# Schematico.net
KiCad netlist of a schematic drawn in EAGLE
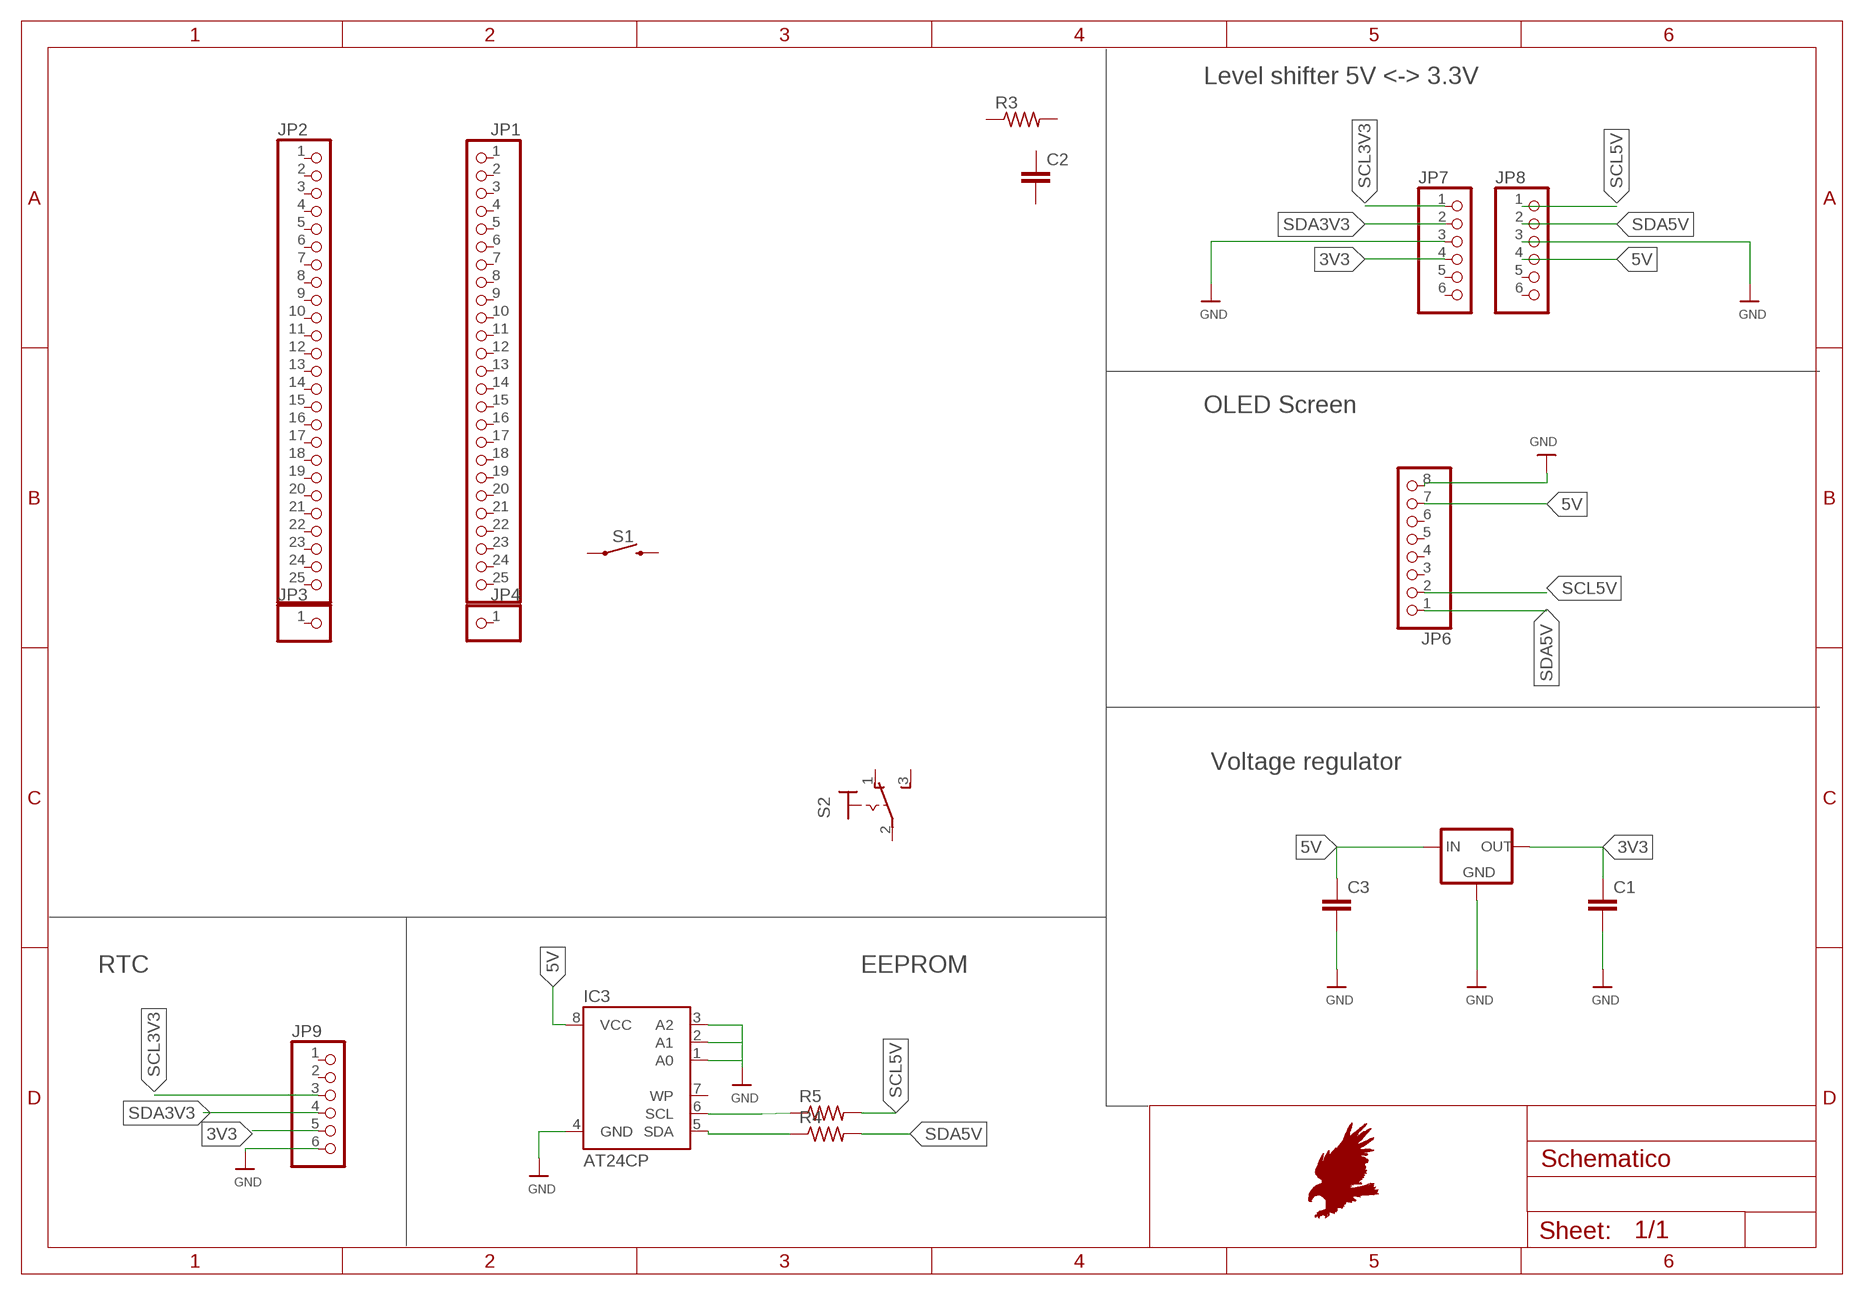
[diagram p0: schematic, sheet 1]

(export (version "E")
  (design (tool "Eeschema 10.0.6"))
  (components
    (comp (ref "C1")
      (value "C2,5-3")
      (footprint "eagle-import:C2.5-3")
      (libsource (lib "eagle-import") (part "C2,5-3"))
    )
    (comp (ref "C2")
      (value "C2,5-3")
      (footprint "eagle-import:C2.5-3")
      (libsource (lib "eagle-import") (part "C2,5-3"))
    )
    (comp (ref "C3")
      (value "C2,5-3")
      (footprint "eagle-import:C2.5-3")
      (libsource (lib "eagle-import") (part "C2,5-3"))
    )
    (comp (ref "IC2")
      (value "78XXS")
      (footprint "eagle-import:78XXS")
      (libsource (lib "eagle-import") (part "78XXS"))
    )
    (comp (ref "IC3")
      (value "AT24CP")
      (footprint "eagle-import:DIL08")
      (fields (field (name "MPN") "AT24C1024BW-SH-B"))
      (libsource (lib "eagle-import") (part "AT24CP"))
    )
    (comp (ref "JP1")
      (value "PINHD-1X25")
      (footprint "eagle-import:1X25")
      (libsource (lib "eagle-import") (part "PINHD-1X25"))
    )
    (comp (ref "JP2")
      (value "PINHD-1X25")
      (footprint "eagle-import:1X25")
      (libsource (lib "eagle-import") (part "PINHD-1X25"))
    )
    (comp (ref "JP3")
      (value "PINHD-1X1")
      (footprint "eagle-import:1X01")
      (libsource (lib "eagle-import") (part "PINHD-1X1"))
    )
    (comp (ref "JP4")
      (value "PINHD-1X1")
      (footprint "eagle-import:1X01")
      (libsource (lib "eagle-import") (part "PINHD-1X1"))
    )
    (comp (ref "JP6")
      (value "PINHD-1X8")
      (footprint "eagle-import:1X08")
      (libsource (lib "eagle-import") (part "PINHD-1X8"))
    )
    (comp (ref "JP7")
      (value "PINHD-1X6B")
      (footprint "eagle-import:1X06-BIG")
      (libsource (lib "eagle-import") (part "PINHD-1X6B"))
    )
    (comp (ref "JP8")
      (value "PINHD-1X6B")
      (footprint "eagle-import:1X06-BIG")
      (libsource (lib "eagle-import") (part "PINHD-1X6B"))
    )
    (comp (ref "JP9")
      (value "PINHD-1X6")
      (footprint "eagle-import:1X06")
      (libsource (lib "eagle-import") (part "pinhead_325_PINHD-1X6"))
    )
    (comp (ref "R3")
      (value "R-US_0204/7")
      (footprint "eagle-import:0204_7")
      (libsource (lib "eagle-import") (part "R-US_0204/7"))
    )
    (comp (ref "R4")
      (value "R-US_0204/7")
      (footprint "eagle-import:0204_7")
      (libsource (lib "eagle-import") (part "R-US_0204/7"))
    )
    (comp (ref "R5")
      (value "R-US_0204/7")
      (footprint "eagle-import:0204_7")
      (libsource (lib "eagle-import") (part "R-US_0204/7"))
    )
    (comp (ref "S1")
      (value "MOMENTARY-SWITCH-SPST-PTH-6.0MM")
      (footprint "eagle-import:TACTILE_SWITCH_PTH_6.0MM")
      (libsource (lib "eagle-import") (part "MOMENTARY-SWITCH-SPST-PTH-6.0MM"))
    )
    (comp (ref "S2")
      (value "320-916")
      (footprint "eagle-import:320-916")
      (libsource (lib "eagle-import") (part "320-916"))
    )
  )
  (nets
    (net (code "1") (name "3V3") (class "Default")
      (node (ref "C1") (pin "1") (pinfunction "1_1") (pintype "passive"))
      (node (ref "IC2") (pin "OUT") (pinfunction "OUT_OUT") (pintype "passive"))
      (node (ref "JP7") (pin "4") (pinfunction "4_4") (pintype "passive"))
      (node (ref "JP9") (pin "5") (pinfunction "5_5") (pintype "passive"))
    )
    (net (code "2") (name "5V") (class "Default")
      (node (ref "C3") (pin "1") (pinfunction "1_1") (pintype "passive"))
      (node (ref "IC2") (pin "IN") (pinfunction "IN_IN") (pintype "input"))
      (node (ref "IC3") (pin "8") (pinfunction "VCC_8") (pintype "power_in"))
      (node (ref "JP6") (pin "7") (pinfunction "7_7") (pintype "passive"))
      (node (ref "JP8") (pin "4") (pinfunction "4_4") (pintype "passive"))
    )
    (net (code "3") (name "GND") (class "Default")
      (node (ref "C1") (pin "2") (pinfunction "2_2") (pintype "passive"))
      (node (ref "C3") (pin "2") (pinfunction "2_2") (pintype "passive"))
      (node (ref "IC2") (pin "GND") (pinfunction "GND_GND") (pintype "input"))
      (node (ref "IC3") (pin "1") (pinfunction "A0_1") (pintype "input"))
      (node (ref "IC3") (pin "2") (pinfunction "A1_2") (pintype "input"))
      (node (ref "IC3") (pin "3") (pinfunction "A2_3") (pintype "input"))
      (node (ref "IC3") (pin "4") (pinfunction "GND_4") (pintype "power_in"))
      (node (ref "JP6") (pin "8") (pinfunction "8_8") (pintype "passive"))
      (node (ref "JP7") (pin "3") (pinfunction "3_3") (pintype "passive"))
      (node (ref "JP8") (pin "3") (pinfunction "3_3") (pintype "passive"))
      (node (ref "JP9") (pin "6") (pinfunction "6_6") (pintype "passive"))
    )
    (net (code "4") (name "Net-(IC3-SCL)") (class "Default")
      (node (ref "IC3") (pin "6") (pinfunction "SCL_6") (pintype "bidirectional"))
      (node (ref "R5") (pin "1") (pinfunction "1_1") (pintype "passive"))
    )
    (net (code "5") (name "Net-(IC3-SDA)") (class "Default")
      (node (ref "IC3") (pin "5") (pinfunction "SDA_5") (pintype "bidirectional"))
      (node (ref "R4") (pin "1") (pinfunction "1_1") (pintype "passive"))
    )
    (net (code "6") (name "SCL3V3") (class "Default")
      (node (ref "JP7") (pin "1") (pinfunction "1_1") (pintype "passive"))
      (node (ref "JP9") (pin "3") (pinfunction "3_3") (pintype "passive"))
    )
    (net (code "7") (name "SCL5V") (class "Default")
      (node (ref "JP6") (pin "2") (pinfunction "2_2") (pintype "passive"))
      (node (ref "JP8") (pin "1") (pinfunction "1_1") (pintype "passive"))
      (node (ref "R5") (pin "2") (pinfunction "2_2") (pintype "passive"))
    )
    (net (code "8") (name "SDA3V3") (class "Default")
      (node (ref "JP7") (pin "2") (pinfunction "2_2") (pintype "passive"))
      (node (ref "JP9") (pin "4") (pinfunction "4_4") (pintype "passive"))
    )
    (net (code "9") (name "SDA5V") (class "Default")
      (node (ref "JP6") (pin "1") (pinfunction "1_1") (pintype "passive"))
      (node (ref "JP8") (pin "2") (pinfunction "2_2") (pintype "passive"))
      (node (ref "R4") (pin "2") (pinfunction "2_2") (pintype "passive"))
    )
    (net (code "10") (name "unconnected-(C2-Pad1)") (class "Default")
      (node (ref "C2") (pin "1") (pinfunction "1_1") (pintype "passive"))
    )
    (net (code "11") (name "unconnected-(C2-Pad2)") (class "Default")
      (node (ref "C2") (pin "2") (pinfunction "2_2") (pintype "passive"))
    )
    (net (code "12") (name "unconnected-(IC3-WP-Pad7)") (class "Default")
      (node (ref "IC3") (pin "7") (pinfunction "WP_7") (pintype "input"))
    )
    (net (code "13") (name "unconnected-(JP1-Pad1)") (class "Default")
      (node (ref "JP1") (pin "1") (pinfunction "1_1") (pintype "passive"))
    )
    (net (code "14") (name "unconnected-(JP1-Pad2)") (class "Default")
      (node (ref "JP1") (pin "2") (pinfunction "2_2") (pintype "passive"))
    )
    (net (code "15") (name "unconnected-(JP1-Pad3)") (class "Default")
      (node (ref "JP1") (pin "3") (pinfunction "3_3") (pintype "passive"))
    )
    (net (code "16") (name "unconnected-(JP1-Pad4)") (class "Default")
      (node (ref "JP1") (pin "4") (pinfunction "4_4") (pintype "passive"))
    )
    (net (code "17") (name "unconnected-(JP1-Pad5)") (class "Default")
      (node (ref "JP1") (pin "5") (pinfunction "5_5") (pintype "passive"))
    )
    (net (code "18") (name "unconnected-(JP1-Pad6)") (class "Default")
      (node (ref "JP1") (pin "6") (pinfunction "6_6") (pintype "passive"))
    )
    (net (code "19") (name "unconnected-(JP1-Pad7)") (class "Default")
      (node (ref "JP1") (pin "7") (pinfunction "7_7") (pintype "passive"))
    )
    (net (code "20") (name "unconnected-(JP1-Pad8)") (class "Default")
      (node (ref "JP1") (pin "8") (pinfunction "8_8") (pintype "passive"))
    )
    (net (code "21") (name "unconnected-(JP1-Pad9)") (class "Default")
      (node (ref "JP1") (pin "9") (pinfunction "9_9") (pintype "passive"))
    )
    (net (code "22") (name "unconnected-(JP1-Pad10)") (class "Default")
      (node (ref "JP1") (pin "10") (pinfunction "10_10") (pintype "passive"))
    )
    (net (code "23") (name "unconnected-(JP1-Pad11)") (class "Default")
      (node (ref "JP1") (pin "11") (pinfunction "11_11") (pintype "passive"))
    )
    (net (code "24") (name "unconnected-(JP1-Pad12)") (class "Default")
      (node (ref "JP1") (pin "12") (pinfunction "12_12") (pintype "passive"))
    )
    (net (code "25") (name "unconnected-(JP1-Pad13)") (class "Default")
      (node (ref "JP1") (pin "13") (pinfunction "13_13") (pintype "passive"))
    )
    (net (code "26") (name "unconnected-(JP1-Pad14)") (class "Default")
      (node (ref "JP1") (pin "14") (pinfunction "14_14") (pintype "passive"))
    )
    (net (code "27") (name "unconnected-(JP1-Pad15)") (class "Default")
      (node (ref "JP1") (pin "15") (pinfunction "15_15") (pintype "passive"))
    )
    (net (code "28") (name "unconnected-(JP1-Pad16)") (class "Default")
      (node (ref "JP1") (pin "16") (pinfunction "16_16") (pintype "passive"))
    )
    (net (code "29") (name "unconnected-(JP1-Pad17)") (class "Default")
      (node (ref "JP1") (pin "17") (pinfunction "17_17") (pintype "passive"))
    )
    (net (code "30") (name "unconnected-(JP1-Pad18)") (class "Default")
      (node (ref "JP1") (pin "18") (pinfunction "18_18") (pintype "passive"))
    )
    (net (code "31") (name "unconnected-(JP1-Pad19)") (class "Default")
      (node (ref "JP1") (pin "19") (pinfunction "19_19") (pintype "passive"))
    )
    (net (code "32") (name "unconnected-(JP1-Pad20)") (class "Default")
      (node (ref "JP1") (pin "20") (pinfunction "20_20") (pintype "passive"))
    )
    (net (code "33") (name "unconnected-(JP1-Pad21)") (class "Default")
      (node (ref "JP1") (pin "21") (pinfunction "21_21") (pintype "passive"))
    )
    (net (code "34") (name "unconnected-(JP1-Pad22)") (class "Default")
      (node (ref "JP1") (pin "22") (pinfunction "22_22") (pintype "passive"))
    )
    (net (code "35") (name "unconnected-(JP1-Pad23)") (class "Default")
      (node (ref "JP1") (pin "23") (pinfunction "23_23") (pintype "passive"))
    )
    (net (code "36") (name "unconnected-(JP1-Pad24)") (class "Default")
      (node (ref "JP1") (pin "24") (pinfunction "24_24") (pintype "passive"))
    )
    (net (code "37") (name "unconnected-(JP1-Pad25)") (class "Default")
      (node (ref "JP1") (pin "25") (pinfunction "25_25") (pintype "passive"))
    )
    (net (code "38") (name "unconnected-(JP2-Pad1)") (class "Default")
      (node (ref "JP2") (pin "1") (pinfunction "1_1") (pintype "passive"))
    )
    (net (code "39") (name "unconnected-(JP2-Pad2)") (class "Default")
      (node (ref "JP2") (pin "2") (pinfunction "2_2") (pintype "passive"))
    )
    (net (code "40") (name "unconnected-(JP2-Pad3)") (class "Default")
      (node (ref "JP2") (pin "3") (pinfunction "3_3") (pintype "passive"))
    )
    (net (code "41") (name "unconnected-(JP2-Pad4)") (class "Default")
      (node (ref "JP2") (pin "4") (pinfunction "4_4") (pintype "passive"))
    )
    (net (code "42") (name "unconnected-(JP2-Pad5)") (class "Default")
      (node (ref "JP2") (pin "5") (pinfunction "5_5") (pintype "passive"))
    )
    (net (code "43") (name "unconnected-(JP2-Pad6)") (class "Default")
      (node (ref "JP2") (pin "6") (pinfunction "6_6") (pintype "passive"))
    )
    (net (code "44") (name "unconnected-(JP2-Pad7)") (class "Default")
      (node (ref "JP2") (pin "7") (pinfunction "7_7") (pintype "passive"))
    )
    (net (code "45") (name "unconnected-(JP2-Pad8)") (class "Default")
      (node (ref "JP2") (pin "8") (pinfunction "8_8") (pintype "passive"))
    )
    (net (code "46") (name "unconnected-(JP2-Pad9)") (class "Default")
      (node (ref "JP2") (pin "9") (pinfunction "9_9") (pintype "passive"))
    )
    (net (code "47") (name "unconnected-(JP2-Pad10)") (class "Default")
      (node (ref "JP2") (pin "10") (pinfunction "10_10") (pintype "passive"))
    )
    (net (code "48") (name "unconnected-(JP2-Pad11)") (class "Default")
      (node (ref "JP2") (pin "11") (pinfunction "11_11") (pintype "passive"))
    )
    (net (code "49") (name "unconnected-(JP2-Pad12)") (class "Default")
      (node (ref "JP2") (pin "12") (pinfunction "12_12") (pintype "passive"))
    )
    (net (code "50") (name "unconnected-(JP2-Pad13)") (class "Default")
      (node (ref "JP2") (pin "13") (pinfunction "13_13") (pintype "passive"))
    )
    (net (code "51") (name "unconnected-(JP2-Pad14)") (class "Default")
      (node (ref "JP2") (pin "14") (pinfunction "14_14") (pintype "passive"))
    )
    (net (code "52") (name "unconnected-(JP2-Pad15)") (class "Default")
      (node (ref "JP2") (pin "15") (pinfunction "15_15") (pintype "passive"))
    )
    (net (code "53") (name "unconnected-(JP2-Pad16)") (class "Default")
      (node (ref "JP2") (pin "16") (pinfunction "16_16") (pintype "passive"))
    )
    (net (code "54") (name "unconnected-(JP2-Pad17)") (class "Default")
      (node (ref "JP2") (pin "17") (pinfunction "17_17") (pintype "passive"))
    )
    (net (code "55") (name "unconnected-(JP2-Pad18)") (class "Default")
      (node (ref "JP2") (pin "18") (pinfunction "18_18") (pintype "passive"))
    )
    (net (code "56") (name "unconnected-(JP2-Pad19)") (class "Default")
      (node (ref "JP2") (pin "19") (pinfunction "19_19") (pintype "passive"))
    )
    (net (code "57") (name "unconnected-(JP2-Pad20)") (class "Default")
      (node (ref "JP2") (pin "20") (pinfunction "20_20") (pintype "passive"))
    )
    (net (code "58") (name "unconnected-(JP2-Pad21)") (class "Default")
      (node (ref "JP2") (pin "21") (pinfunction "21_21") (pintype "passive"))
    )
    (net (code "59") (name "unconnected-(JP2-Pad22)") (class "Default")
      (node (ref "JP2") (pin "22") (pinfunction "22_22") (pintype "passive"))
    )
    (net (code "60") (name "unconnected-(JP2-Pad23)") (class "Default")
      (node (ref "JP2") (pin "23") (pinfunction "23_23") (pintype "passive"))
    )
    (net (code "61") (name "unconnected-(JP2-Pad24)") (class "Default")
      (node (ref "JP2") (pin "24") (pinfunction "24_24") (pintype "passive"))
    )
    (net (code "62") (name "unconnected-(JP2-Pad25)") (class "Default")
      (node (ref "JP2") (pin "25") (pinfunction "25_25") (pintype "passive"))
    )
    (net (code "63") (name "unconnected-(JP3-Pad1)") (class "Default")
      (node (ref "JP3") (pin "1") (pinfunction "1_1") (pintype "passive"))
    )
    (net (code "64") (name "unconnected-(JP4-Pad1)") (class "Default")
      (node (ref "JP4") (pin "1") (pinfunction "1_1") (pintype "passive"))
    )
    (net (code "65") (name "unconnected-(JP6-Pad3)") (class "Default")
      (node (ref "JP6") (pin "3") (pinfunction "3_3") (pintype "passive"))
    )
    (net (code "66") (name "unconnected-(JP6-Pad4)") (class "Default")
      (node (ref "JP6") (pin "4") (pinfunction "4_4") (pintype "passive"))
    )
    (net (code "67") (name "unconnected-(JP6-Pad5)") (class "Default")
      (node (ref "JP6") (pin "5") (pinfunction "5_5") (pintype "passive"))
    )
    (net (code "68") (name "unconnected-(JP6-Pad6)") (class "Default")
      (node (ref "JP6") (pin "6") (pinfunction "6_6") (pintype "passive"))
    )
    (net (code "69") (name "unconnected-(JP7-Pad5)") (class "Default")
      (node (ref "JP7") (pin "5") (pinfunction "5_5") (pintype "passive"))
    )
    (net (code "70") (name "unconnected-(JP7-Pad6)") (class "Default")
      (node (ref "JP7") (pin "6") (pinfunction "6_6") (pintype "passive"))
    )
    (net (code "71") (name "unconnected-(JP8-Pad5)") (class "Default")
      (node (ref "JP8") (pin "5") (pinfunction "5_5") (pintype "passive"))
    )
    (net (code "72") (name "unconnected-(JP8-Pad6)") (class "Default")
      (node (ref "JP8") (pin "6") (pinfunction "6_6") (pintype "passive"))
    )
    (net (code "73") (name "unconnected-(JP9-Pad1)") (class "Default")
      (node (ref "JP9") (pin "1") (pinfunction "1_1") (pintype "passive"))
    )
    (net (code "74") (name "unconnected-(JP9-Pad2)") (class "Default")
      (node (ref "JP9") (pin "2") (pinfunction "2_2") (pintype "passive"))
    )
    (net (code "75") (name "unconnected-(R3-Pad1)") (class "Default")
      (node (ref "R3") (pin "1") (pinfunction "1_1") (pintype "passive"))
    )
    (net (code "76") (name "unconnected-(R3-Pad2)") (class "Default")
      (node (ref "R3") (pin "2") (pinfunction "2_2") (pintype "passive"))
    )
    (net (code "77") (name "unconnected-(S1-2-Pad3)") (class "Default")
      (node (ref "S1") (pin "3") (pinfunction "2_3") (pintype "passive"))
    )
    (net (code "78") (name "unconnected-(S1-Pad1)") (class "Default")
      (node (ref "S1") (pin "1") (pinfunction "1_1") (pintype "passive"))
    )
    (net (code "79") (name "unconnected-(S2-O-Pad1)") (class "Default")
      (node (ref "S2") (pin "1") (pinfunction "O_1") (pintype "passive"))
    )
    (net (code "80") (name "unconnected-(S2-P-Pad2)") (class "Default")
      (node (ref "S2") (pin "2") (pinfunction "P_2") (pintype "passive"))
    )
    (net (code "81") (name "unconnected-(S2-S-Pad3)") (class "Default")
      (node (ref "S2") (pin "3") (pinfunction "S_3") (pintype "passive"))
    )
  )
)
